# listwa_z_czujnikami.net
KiCad netlist of a schematic drawn in EAGLE
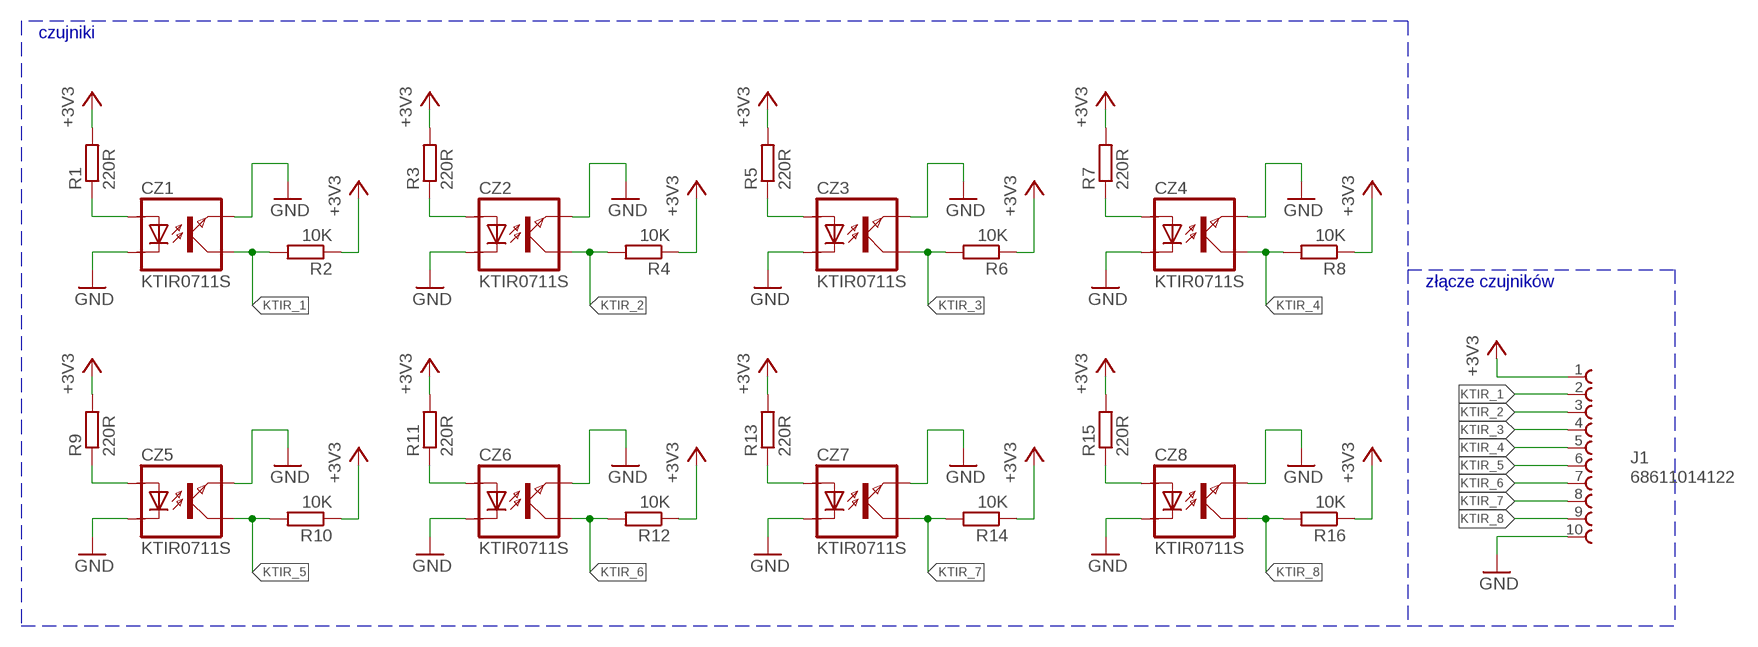
[diagram p0: schematic, sheet 1]

(export (version "E")
  (design (tool "Eeschema 10.0.6"))
  (components
    (comp (ref "CZ1")
      (value "KTIR0711S")
      (footprint "eagle-import:TOP")
      (libsource (lib "eagle-import") (part "KTIR0711S"))
    )
    (comp (ref "CZ2")
      (value "KTIR0711S")
      (footprint "eagle-import:TOP")
      (libsource (lib "eagle-import") (part "KTIR0711S"))
    )
    (comp (ref "CZ3")
      (value "KTIR0711S")
      (footprint "eagle-import:TOP")
      (libsource (lib "eagle-import") (part "KTIR0711S"))
    )
    (comp (ref "CZ4")
      (value "KTIR0711S")
      (footprint "eagle-import:TOP")
      (libsource (lib "eagle-import") (part "KTIR0711S"))
    )
    (comp (ref "CZ5")
      (value "KTIR0711S")
      (footprint "eagle-import:TOP")
      (libsource (lib "eagle-import") (part "KTIR0711S"))
    )
    (comp (ref "CZ6")
      (value "KTIR0711S")
      (footprint "eagle-import:TOP")
      (libsource (lib "eagle-import") (part "KTIR0711S"))
    )
    (comp (ref "CZ7")
      (value "KTIR0711S")
      (footprint "eagle-import:TOP")
      (libsource (lib "eagle-import") (part "KTIR0711S"))
    )
    (comp (ref "CZ8")
      (value "KTIR0711S")
      (footprint "eagle-import:TOP")
      (libsource (lib "eagle-import") (part "KTIR0711S"))
    )
    (comp (ref "J1")
      (value "68611014122")
      (footprint "eagle-import:68611014122")
      (libsource (lib "eagle-import") (part "68611014122"))
    )
    (comp (ref "R1")
      (value "220R")
      (footprint "eagle-import:R0805")
      (libsource (lib "eagle-import") (part "R-EU_R0805"))
    )
    (comp (ref "R2")
      (value "10K")
      (footprint "eagle-import:R0805")
      (libsource (lib "eagle-import") (part "R-EU_R0805"))
    )
    (comp (ref "R3")
      (value "220R")
      (footprint "eagle-import:R0805")
      (libsource (lib "eagle-import") (part "R-EU_R0805"))
    )
    (comp (ref "R4")
      (value "10K")
      (footprint "eagle-import:R0805")
      (libsource (lib "eagle-import") (part "R-EU_R0805"))
    )
    (comp (ref "R5")
      (value "220R")
      (footprint "eagle-import:R0805")
      (libsource (lib "eagle-import") (part "R-EU_R0805"))
    )
    (comp (ref "R6")
      (value "10K")
      (footprint "eagle-import:R0805")
      (libsource (lib "eagle-import") (part "R-EU_R0805"))
    )
    (comp (ref "R7")
      (value "220R")
      (footprint "eagle-import:R0805")
      (libsource (lib "eagle-import") (part "R-EU_R0805"))
    )
    (comp (ref "R8")
      (value "10K")
      (footprint "eagle-import:R0805")
      (libsource (lib "eagle-import") (part "R-EU_R0805"))
    )
    (comp (ref "R9")
      (value "220R")
      (footprint "eagle-import:R0805")
      (libsource (lib "eagle-import") (part "R-EU_R0805"))
    )
    (comp (ref "R10")
      (value "10K")
      (footprint "eagle-import:R0805")
      (libsource (lib "eagle-import") (part "R-EU_R0805"))
    )
    (comp (ref "R11")
      (value "220R")
      (footprint "eagle-import:R0805")
      (libsource (lib "eagle-import") (part "R-EU_R0805"))
    )
    (comp (ref "R12")
      (value "10K")
      (footprint "eagle-import:R0805")
      (libsource (lib "eagle-import") (part "R-EU_R0805"))
    )
    (comp (ref "R13")
      (value "220R")
      (footprint "eagle-import:R0805")
      (libsource (lib "eagle-import") (part "R-EU_R0805"))
    )
    (comp (ref "R14")
      (value "10K")
      (footprint "eagle-import:R0805")
      (libsource (lib "eagle-import") (part "R-EU_R0805"))
    )
    (comp (ref "R15")
      (value "220R")
      (footprint "eagle-import:R0805")
      (libsource (lib "eagle-import") (part "R-EU_R0805"))
    )
    (comp (ref "R16")
      (value "10K")
      (footprint "eagle-import:R0805")
      (libsource (lib "eagle-import") (part "R-EU_R0805"))
    )
  )
  (nets
    (net (code "1") (name "+3V3") (class "Default")
      (node (ref "J1") (pin "1") (pinfunction "1_1") (pintype "passive"))
      (node (ref "R1") (pin "2") (pinfunction "2_2") (pintype "passive"))
      (node (ref "R10") (pin "1") (pinfunction "1_1") (pintype "passive"))
      (node (ref "R11") (pin "2") (pinfunction "2_2") (pintype "passive"))
      (node (ref "R12") (pin "1") (pinfunction "1_1") (pintype "passive"))
      (node (ref "R13") (pin "2") (pinfunction "2_2") (pintype "passive"))
      (node (ref "R14") (pin "1") (pinfunction "1_1") (pintype "passive"))
      (node (ref "R15") (pin "2") (pinfunction "2_2") (pintype "passive"))
      (node (ref "R16") (pin "1") (pinfunction "1_1") (pintype "passive"))
      (node (ref "R2") (pin "1") (pinfunction "1_1") (pintype "passive"))
      (node (ref "R3") (pin "2") (pinfunction "2_2") (pintype "passive"))
      (node (ref "R4") (pin "1") (pinfunction "1_1") (pintype "passive"))
      (node (ref "R5") (pin "2") (pinfunction "2_2") (pintype "passive"))
      (node (ref "R6") (pin "1") (pinfunction "1_1") (pintype "passive"))
      (node (ref "R7") (pin "2") (pinfunction "2_2") (pintype "passive"))
      (node (ref "R8") (pin "1") (pinfunction "1_1") (pintype "passive"))
      (node (ref "R9") (pin "2") (pinfunction "2_2") (pintype "passive"))
    )
    (net (code "2") (name "GND") (class "Default")
      (node (ref "CZ1") (pin "EMITER") (pinfunction "EMITER_EMITER") (pintype "bidirectional"))
      (node (ref "CZ1") (pin "KATODA") (pinfunction "KATODA_KATODA") (pintype "passive"))
      (node (ref "CZ2") (pin "EMITER") (pinfunction "EMITER_EMITER") (pintype "bidirectional"))
      (node (ref "CZ2") (pin "KATODA") (pinfunction "KATODA_KATODA") (pintype "passive"))
      (node (ref "CZ3") (pin "EMITER") (pinfunction "EMITER_EMITER") (pintype "bidirectional"))
      (node (ref "CZ3") (pin "KATODA") (pinfunction "KATODA_KATODA") (pintype "passive"))
      (node (ref "CZ4") (pin "EMITER") (pinfunction "EMITER_EMITER") (pintype "bidirectional"))
      (node (ref "CZ4") (pin "KATODA") (pinfunction "KATODA_KATODA") (pintype "passive"))
      (node (ref "CZ5") (pin "EMITER") (pinfunction "EMITER_EMITER") (pintype "bidirectional"))
      (node (ref "CZ5") (pin "KATODA") (pinfunction "KATODA_KATODA") (pintype "passive"))
      (node (ref "CZ6") (pin "EMITER") (pinfunction "EMITER_EMITER") (pintype "bidirectional"))
      (node (ref "CZ6") (pin "KATODA") (pinfunction "KATODA_KATODA") (pintype "passive"))
      (node (ref "CZ7") (pin "EMITER") (pinfunction "EMITER_EMITER") (pintype "bidirectional"))
      (node (ref "CZ7") (pin "KATODA") (pinfunction "KATODA_KATODA") (pintype "passive"))
      (node (ref "CZ8") (pin "EMITER") (pinfunction "EMITER_EMITER") (pintype "bidirectional"))
      (node (ref "CZ8") (pin "KATODA") (pinfunction "KATODA_KATODA") (pintype "passive"))
      (node (ref "J1") (pin "10") (pinfunction "10_10") (pintype "passive"))
    )
    (net (code "3") (name "KTIR_1") (class "Default")
      (node (ref "CZ1") (pin "KOLEKTOR") (pinfunction "KOLEKTOR_KOLEKTOR") (pintype "bidirectional"))
      (node (ref "J1") (pin "2") (pinfunction "2_2") (pintype "passive"))
      (node (ref "R2") (pin "2") (pinfunction "2_2") (pintype "passive"))
    )
    (net (code "4") (name "KTIR_2") (class "Default")
      (node (ref "CZ2") (pin "KOLEKTOR") (pinfunction "KOLEKTOR_KOLEKTOR") (pintype "bidirectional"))
      (node (ref "J1") (pin "3") (pinfunction "3_3") (pintype "passive"))
      (node (ref "R4") (pin "2") (pinfunction "2_2") (pintype "passive"))
    )
    (net (code "5") (name "KTIR_3") (class "Default")
      (node (ref "CZ3") (pin "KOLEKTOR") (pinfunction "KOLEKTOR_KOLEKTOR") (pintype "bidirectional"))
      (node (ref "J1") (pin "4") (pinfunction "4_4") (pintype "passive"))
      (node (ref "R6") (pin "2") (pinfunction "2_2") (pintype "passive"))
    )
    (net (code "6") (name "KTIR_4") (class "Default")
      (node (ref "CZ4") (pin "KOLEKTOR") (pinfunction "KOLEKTOR_KOLEKTOR") (pintype "bidirectional"))
      (node (ref "J1") (pin "5") (pinfunction "5_5") (pintype "passive"))
      (node (ref "R8") (pin "2") (pinfunction "2_2") (pintype "passive"))
    )
    (net (code "7") (name "KTIR_5") (class "Default")
      (node (ref "CZ5") (pin "KOLEKTOR") (pinfunction "KOLEKTOR_KOLEKTOR") (pintype "bidirectional"))
      (node (ref "J1") (pin "6") (pinfunction "6_6") (pintype "passive"))
      (node (ref "R10") (pin "2") (pinfunction "2_2") (pintype "passive"))
    )
    (net (code "8") (name "KTIR_6") (class "Default")
      (node (ref "CZ6") (pin "KOLEKTOR") (pinfunction "KOLEKTOR_KOLEKTOR") (pintype "bidirectional"))
      (node (ref "J1") (pin "7") (pinfunction "7_7") (pintype "passive"))
      (node (ref "R12") (pin "2") (pinfunction "2_2") (pintype "passive"))
    )
    (net (code "9") (name "KTIR_7") (class "Default")
      (node (ref "CZ7") (pin "KOLEKTOR") (pinfunction "KOLEKTOR_KOLEKTOR") (pintype "bidirectional"))
      (node (ref "J1") (pin "8") (pinfunction "8_8") (pintype "passive"))
      (node (ref "R14") (pin "2") (pinfunction "2_2") (pintype "passive"))
    )
    (net (code "10") (name "KTIR_8") (class "Default")
      (node (ref "CZ8") (pin "KOLEKTOR") (pinfunction "KOLEKTOR_KOLEKTOR") (pintype "bidirectional"))
      (node (ref "J1") (pin "9") (pinfunction "9_9") (pintype "passive"))
      (node (ref "R16") (pin "2") (pinfunction "2_2") (pintype "passive"))
    )
    (net (code "11") (name "Net-(CZ1-PadANODA)") (class "Default")
      (node (ref "CZ1") (pin "ANODA") (pinfunction "ANODA_ANODA") (pintype "passive"))
      (node (ref "R1") (pin "1") (pinfunction "1_1") (pintype "passive"))
    )
    (net (code "12") (name "Net-(CZ2-PadANODA)") (class "Default")
      (node (ref "CZ2") (pin "ANODA") (pinfunction "ANODA_ANODA") (pintype "passive"))
      (node (ref "R3") (pin "1") (pinfunction "1_1") (pintype "passive"))
    )
    (net (code "13") (name "Net-(CZ3-PadANODA)") (class "Default")
      (node (ref "CZ3") (pin "ANODA") (pinfunction "ANODA_ANODA") (pintype "passive"))
      (node (ref "R5") (pin "1") (pinfunction "1_1") (pintype "passive"))
    )
    (net (code "14") (name "Net-(CZ4-PadANODA)") (class "Default")
      (node (ref "CZ4") (pin "ANODA") (pinfunction "ANODA_ANODA") (pintype "passive"))
      (node (ref "R7") (pin "1") (pinfunction "1_1") (pintype "passive"))
    )
    (net (code "15") (name "Net-(CZ5-PadANODA)") (class "Default")
      (node (ref "CZ5") (pin "ANODA") (pinfunction "ANODA_ANODA") (pintype "passive"))
      (node (ref "R9") (pin "1") (pinfunction "1_1") (pintype "passive"))
    )
    (net (code "16") (name "Net-(CZ6-PadANODA)") (class "Default")
      (node (ref "CZ6") (pin "ANODA") (pinfunction "ANODA_ANODA") (pintype "passive"))
      (node (ref "R11") (pin "1") (pinfunction "1_1") (pintype "passive"))
    )
    (net (code "17") (name "Net-(CZ7-PadANODA)") (class "Default")
      (node (ref "CZ7") (pin "ANODA") (pinfunction "ANODA_ANODA") (pintype "passive"))
      (node (ref "R13") (pin "1") (pinfunction "1_1") (pintype "passive"))
    )
    (net (code "18") (name "Net-(CZ8-PadANODA)") (class "Default")
      (node (ref "CZ8") (pin "ANODA") (pinfunction "ANODA_ANODA") (pintype "passive"))
      (node (ref "R15") (pin "1") (pinfunction "1_1") (pintype "passive"))
    )
  )
)
